# HW2_latest.net
KiCad netlist of a schematic drawn in EAGLE
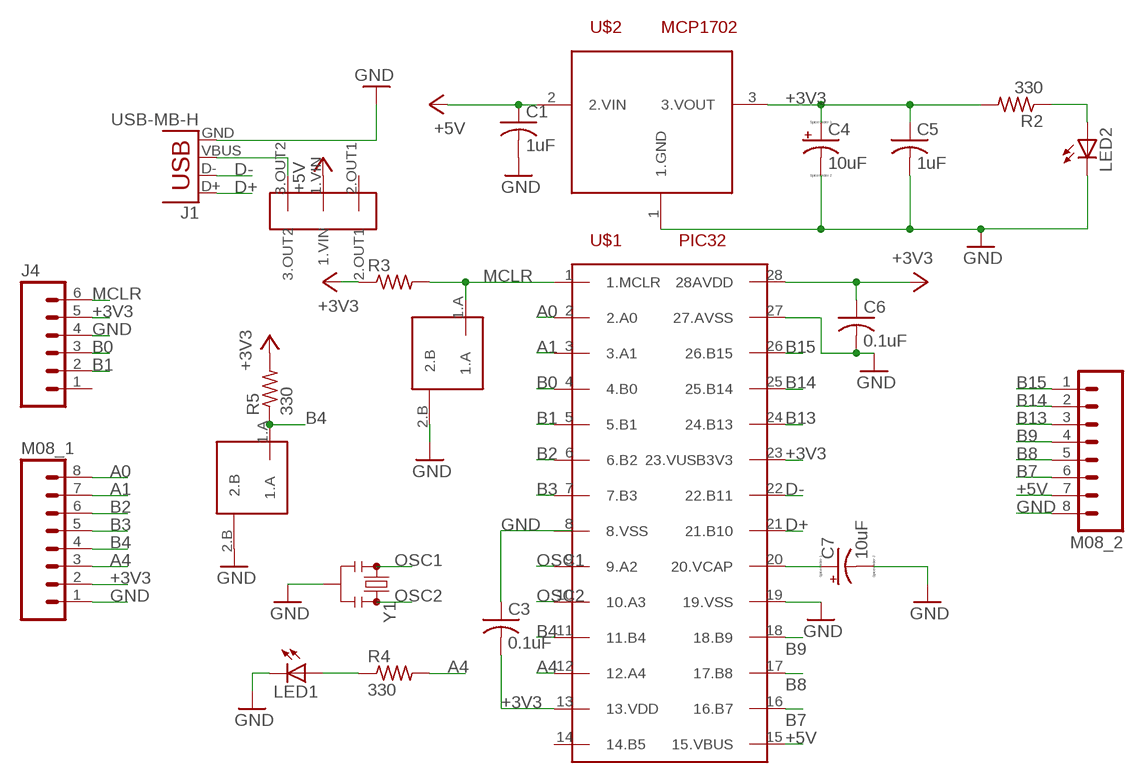
[diagram p0: schematic, sheet 1]

(export (version "E")
  (design (tool "Eeschema 10.0.6"))
  (components
    (comp (ref "C1")
      (value "1uF")
      (footprint "eagle-import:C025-024X044")
      (libsource (lib "eagle-import") (part "C-US025-024X044"))
    )
    (comp (ref "C3")
      (value "0.1uF")
      (footprint "eagle-import:C025-024X044")
      (libsource (lib "eagle-import") (part "C-US025-024X044"))
    )
    (comp (ref "C4")
      (value "10uF")
      (footprint "eagle-import:TT2D4")
      (libsource (lib "eagle-import") (part "CPOL-USTT2D4"))
    )
    (comp (ref "C5")
      (value "1uF")
      (footprint "eagle-import:C025-024X044")
      (libsource (lib "eagle-import") (part "C-US025-024X044"))
    )
    (comp (ref "C6")
      (value "0.1uF")
      (footprint "eagle-import:C025-024X044")
      (libsource (lib "eagle-import") (part "C-US025-024X044"))
    )
    (comp (ref "C7")
      (value "10uF")
      (footprint "eagle-import:TT2D4")
      (libsource (lib "eagle-import") (part "CPOL-USTT2D4"))
    )
    (comp (ref "J1")
      (value "USB-MB-H")
      (footprint "eagle-import:USB-MB-H")
      (libsource (lib "eagle-import") (part "USB-MB-H"))
    )
    (comp (ref "J4")
      (value "M06SILK_FEMALE_PTH")
      (footprint "eagle-import:1X06")
      (libsource (lib "eagle-import") (part "M06SILK_FEMALE_PTH"))
    )
    (comp (ref "LED1")
      (value "LED3MM")
      (footprint "eagle-import:LED3MM")
      (libsource (lib "eagle-import") (part "LED3MM"))
    )
    (comp (ref "LED2")
      (value "LED3MM")
      (footprint "eagle-import:LED3MM")
      (libsource (lib "eagle-import") (part "LED3MM"))
    )
    (comp (ref "M08_1")
      (value "M08")
      (footprint "eagle-import:1X08_ROUND")
      (libsource (lib "eagle-import") (part "M08"))
    )
    (comp (ref "M08_2")
      (value "M08")
      (footprint "eagle-import:1X08_ROUND")
      (libsource (lib "eagle-import") (part "M08"))
    )
    (comp (ref "R2")
      (value "330")
      (footprint "eagle-import:0207_10")
      (libsource (lib "eagle-import") (part "R-US_0207/10"))
    )
    (comp (ref "R3")
      (value "R-US_0207/10")
      (footprint "eagle-import:0207_10")
      (libsource (lib "eagle-import") (part "R-US_0207/10"))
    )
    (comp (ref "R4")
      (value "330")
      (footprint "eagle-import:0207_10")
      (libsource (lib "eagle-import") (part "R-US_0207/10"))
    )
    (comp (ref "R5")
      (value "330")
      (footprint "eagle-import:0207_10")
      (libsource (lib "eagle-import") (part "R-US_0207/10"))
    )
    (comp (ref "U$1")
      (value "PIC32")
      (footprint "eagle-import:DIL28-3")
      (libsource (lib "eagle-import") (part "PIC32"))
    )
    (comp (ref "U$2")
      (value "MCP1702")
      (footprint "eagle-import:TO92")
      (libsource (lib "eagle-import") (part "MCP1702"))
    )
    (comp (ref "U$3")
      (value "SLIDE_SWITCH")
      (footprint "eagle-import:SLIDE_SWITCH")
      (libsource (lib "eagle-import") (part "SLIDE_SWITCH"))
    )
    (comp (ref "U$4")
      (value "PUSH_BUTTON")
      (footprint "eagle-import:PUSH_BUTTON")
      (libsource (lib "eagle-import") (part "PUSH_BUTTON"))
    )
    (comp (ref "U$5")
      (value "PUSH_BUTTON")
      (footprint "eagle-import:PUSH_BUTTON")
      (libsource (lib "eagle-import") (part "PUSH_BUTTON"))
    )
    (comp (ref "Y1")
      (value "RESONATORPTH")
      (footprint "eagle-import:RESONATOR-PTH")
      (libsource (lib "eagle-import") (part "RESONATORPTH"))
    )
  )
  (nets
    (net (code "1") (name "+3V3") (class "Default")
      (node (ref "C3") (pin "2") (pinfunction "2_2") (pintype "passive"))
      (node (ref "C4") (pin "+") (pinfunction "+_+") (pintype "passive"))
      (node (ref "C5") (pin "1") (pinfunction "1_1") (pintype "passive"))
      (node (ref "C6") (pin "1") (pinfunction "1_1") (pintype "passive"))
      (node (ref "J4") (pin "5") (pinfunction "5_5") (pintype "passive"))
      (node (ref "M08_1") (pin "2") (pinfunction "2_2") (pintype "passive"))
      (node (ref "R2") (pin "2") (pinfunction "2_2") (pintype "passive"))
      (node (ref "R3") (pin "1") (pinfunction "1_1") (pintype "passive"))
      (node (ref "R5") (pin "2") (pinfunction "2_2") (pintype "passive"))
      (node (ref "U$1") (pin "13") (pinfunction "13.VDD_13") (pintype "bidirectional"))
      (node (ref "U$1") (pin "23") (pinfunction "23.VUSB3V3_23") (pintype "bidirectional"))
      (node (ref "U$1") (pin "28") (pinfunction "28AVDD_28") (pintype "bidirectional"))
      (node (ref "U$2") (pin "3") (pinfunction "3.VOUT_3") (pintype "bidirectional"))
    )
    (net (code "2") (name "+5V") (class "Default")
      (node (ref "C1") (pin "1") (pinfunction "1_1") (pintype "passive"))
      (node (ref "M08_2") (pin "7") (pinfunction "7_7") (pintype "passive"))
      (node (ref "U$1") (pin "15") (pinfunction "15.VBUS_15") (pintype "bidirectional"))
      (node (ref "U$2") (pin "2") (pinfunction "2.VIN_2") (pintype "bidirectional"))
      (node (ref "U$3") (pin "1.VIN") (pinfunction "1.VIN_1.VIN") (pintype "bidirectional"))
    )
    (net (code "3") (name "/A0") (class "Default")
      (node (ref "M08_1") (pin "8") (pinfunction "8_8") (pintype "passive"))
      (node (ref "U$1") (pin "2") (pinfunction "2.A0_2") (pintype "bidirectional"))
    )
    (net (code "4") (name "/A1") (class "Default")
      (node (ref "M08_1") (pin "7") (pinfunction "7_7") (pintype "passive"))
      (node (ref "U$1") (pin "3") (pinfunction "3.A1_3") (pintype "bidirectional"))
    )
    (net (code "5") (name "/A4") (class "Default")
      (node (ref "M08_1") (pin "3") (pinfunction "3_3") (pintype "passive"))
      (node (ref "R4") (pin "2") (pinfunction "2_2") (pintype "passive"))
      (node (ref "U$1") (pin "12") (pinfunction "12.A4_12") (pintype "bidirectional"))
    )
    (net (code "6") (name "/B0") (class "Default")
      (node (ref "J4") (pin "3") (pinfunction "3_3") (pintype "passive"))
      (node (ref "U$1") (pin "4") (pinfunction "4.B0_4") (pintype "bidirectional"))
    )
    (net (code "7") (name "/B1") (class "Default")
      (node (ref "J4") (pin "2") (pinfunction "2_2") (pintype "passive"))
      (node (ref "U$1") (pin "5") (pinfunction "5.B1_5") (pintype "bidirectional"))
    )
    (net (code "8") (name "/B2") (class "Default")
      (node (ref "M08_1") (pin "6") (pinfunction "6_6") (pintype "passive"))
      (node (ref "U$1") (pin "6") (pinfunction "6.B2_6") (pintype "bidirectional"))
    )
    (net (code "9") (name "/B3") (class "Default")
      (node (ref "M08_1") (pin "5") (pinfunction "5_5") (pintype "passive"))
      (node (ref "U$1") (pin "7") (pinfunction "7.B3_7") (pintype "bidirectional"))
    )
    (net (code "10") (name "/B4") (class "Default")
      (node (ref "M08_1") (pin "4") (pinfunction "4_4") (pintype "passive"))
      (node (ref "R5") (pin "1") (pinfunction "1_1") (pintype "passive"))
      (node (ref "U$1") (pin "11") (pinfunction "11.B4_11") (pintype "bidirectional"))
      (node (ref "U$5") (pin "1.A") (pinfunction "1.A_1.A") (pintype "bidirectional"))
    )
    (net (code "11") (name "/B7") (class "Default")
      (node (ref "M08_2") (pin "6") (pinfunction "6_6") (pintype "passive"))
      (node (ref "U$1") (pin "16") (pinfunction "16.B7_16") (pintype "bidirectional"))
    )
    (net (code "12") (name "/B8") (class "Default")
      (node (ref "M08_2") (pin "5") (pinfunction "5_5") (pintype "passive"))
      (node (ref "U$1") (pin "17") (pinfunction "17.B8_17") (pintype "bidirectional"))
    )
    (net (code "13") (name "/B9") (class "Default")
      (node (ref "M08_2") (pin "4") (pinfunction "4_4") (pintype "passive"))
      (node (ref "U$1") (pin "18") (pinfunction "18.B9_18") (pintype "bidirectional"))
    )
    (net (code "14") (name "/B13") (class "Default")
      (node (ref "M08_2") (pin "3") (pinfunction "3_3") (pintype "passive"))
      (node (ref "U$1") (pin "24") (pinfunction "24.B13_24") (pintype "bidirectional"))
    )
    (net (code "15") (name "/B14") (class "Default")
      (node (ref "M08_2") (pin "2") (pinfunction "2_2") (pintype "passive"))
      (node (ref "U$1") (pin "25") (pinfunction "25.B14_25") (pintype "bidirectional"))
    )
    (net (code "16") (name "/B15") (class "Default")
      (node (ref "M08_2") (pin "1") (pinfunction "1_1") (pintype "passive"))
      (node (ref "U$1") (pin "26") (pinfunction "26.B15_26") (pintype "bidirectional"))
    )
    (net (code "17") (name "/D+") (class "Default")
      (node (ref "J1") (pin "D+") (pinfunction "D+_D+") (pintype "bidirectional"))
      (node (ref "U$1") (pin "21") (pinfunction "21.B10_21") (pintype "bidirectional"))
    )
    (net (code "18") (name "/D-") (class "Default")
      (node (ref "J1") (pin "D-") (pinfunction "D-_D-") (pintype "bidirectional"))
      (node (ref "U$1") (pin "22") (pinfunction "22.B11_22") (pintype "bidirectional"))
    )
    (net (code "19") (name "/MCLR") (class "Default")
      (node (ref "J4") (pin "6") (pinfunction "6_6") (pintype "passive"))
      (node (ref "R3") (pin "2") (pinfunction "2_2") (pintype "passive"))
      (node (ref "U$1") (pin "1") (pinfunction "1.MCLR_1") (pintype "bidirectional"))
      (node (ref "U$4") (pin "1.A") (pinfunction "1.A_1.A") (pintype "bidirectional"))
    )
    (net (code "20") (name "/OSC1") (class "Default")
      (node (ref "U$1") (pin "9") (pinfunction "9.A2_9") (pintype "bidirectional"))
      (node (ref "Y1") (pin "1") (pinfunction "1_1") (pintype "passive"))
    )
    (net (code "21") (name "/OSC2") (class "Default")
      (node (ref "U$1") (pin "10") (pinfunction "10.A3_10") (pintype "bidirectional"))
      (node (ref "Y1") (pin "3") (pinfunction "3_3") (pintype "passive"))
    )
    (net (code "22") (name "GND") (class "Default")
      (node (ref "C1") (pin "2") (pinfunction "2_2") (pintype "passive"))
      (node (ref "C3") (pin "1") (pinfunction "1_1") (pintype "passive"))
      (node (ref "C4") (pin "-") (pinfunction "-_-") (pintype "passive"))
      (node (ref "C5") (pin "2") (pinfunction "2_2") (pintype "passive"))
      (node (ref "C6") (pin "2") (pinfunction "2_2") (pintype "passive"))
      (node (ref "C7") (pin "-") (pinfunction "-_-") (pintype "passive"))
      (node (ref "J1") (pin "GND") (pinfunction "GND_GND") (pintype "bidirectional"))
      (node (ref "J4") (pin "4") (pinfunction "4_4") (pintype "passive"))
      (node (ref "LED1") (pin "K") (pinfunction "C_K") (pintype "passive"))
      (node (ref "LED2") (pin "K") (pinfunction "C_K") (pintype "passive"))
      (node (ref "M08_1") (pin "1") (pinfunction "1_1") (pintype "passive"))
      (node (ref "M08_2") (pin "8") (pinfunction "8_8") (pintype "passive"))
      (node (ref "U$1") (pin "19") (pinfunction "19.VSS_19") (pintype "bidirectional"))
      (node (ref "U$1") (pin "27") (pinfunction "27.AVSS_27") (pintype "bidirectional"))
      (node (ref "U$2") (pin "1") (pinfunction "1.GND_1") (pintype "bidirectional"))
      (node (ref "U$4") (pin "2.B") (pinfunction "2.B_2.B") (pintype "bidirectional"))
      (node (ref "U$5") (pin "2.B") (pinfunction "2.B_2.B") (pintype "bidirectional"))
      (node (ref "Y1") (pin "2") (pinfunction "2_2") (pintype "passive"))
    )
    (net (code "23") (name "Net-(J1-PadVBUS)") (class "Default")
      (node (ref "J1") (pin "VBUS") (pinfunction "VBUS_VBUS") (pintype "bidirectional"))
      (node (ref "U$3") (pin "3.OUT2") (pinfunction "3.OUT2_3.OUT2") (pintype "bidirectional"))
    )
    (net (code "24") (name "Net-(LED1-PadA)") (class "Default")
      (node (ref "LED1") (pin "A") (pinfunction "A_A") (pintype "passive"))
      (node (ref "R4") (pin "1") (pinfunction "1_1") (pintype "passive"))
    )
    (net (code "25") (name "Net-(LED2-PadA)") (class "Default")
      (node (ref "LED2") (pin "A") (pinfunction "A_A") (pintype "passive"))
      (node (ref "R2") (pin "1") (pinfunction "1_1") (pintype "passive"))
    )
    (net (code "26") (name "Net-(U$1-20.VCAP)") (class "Default")
      (node (ref "C7") (pin "+") (pinfunction "+_+") (pintype "passive"))
      (node (ref "U$1") (pin "20") (pinfunction "20.VCAP_20") (pintype "bidirectional"))
    )
    (net (code "27") (name "unconnected-(J4-Pad1)") (class "Default")
      (node (ref "J4") (pin "1") (pinfunction "1_1") (pintype "passive"))
    )
    (net (code "28") (name "unconnected-(U$1-8.VSS-Pad8)") (class "Default")
      (node (ref "U$1") (pin "8") (pinfunction "8.VSS_8") (pintype "bidirectional"))
    )
    (net (code "29") (name "unconnected-(U$1-14.B5-Pad14)") (class "Default")
      (node (ref "U$1") (pin "14") (pinfunction "14.B5_14") (pintype "bidirectional"))
    )
    (net (code "30") (name "unconnected-(U$3-Pad2.OUT1)") (class "Default")
      (node (ref "U$3") (pin "2.OUT1") (pinfunction "2.OUT1_2.OUT1") (pintype "bidirectional"))
    )
  )
)
